# Microduino-Core.net
KiCad netlist of a schematic drawn in EAGLE
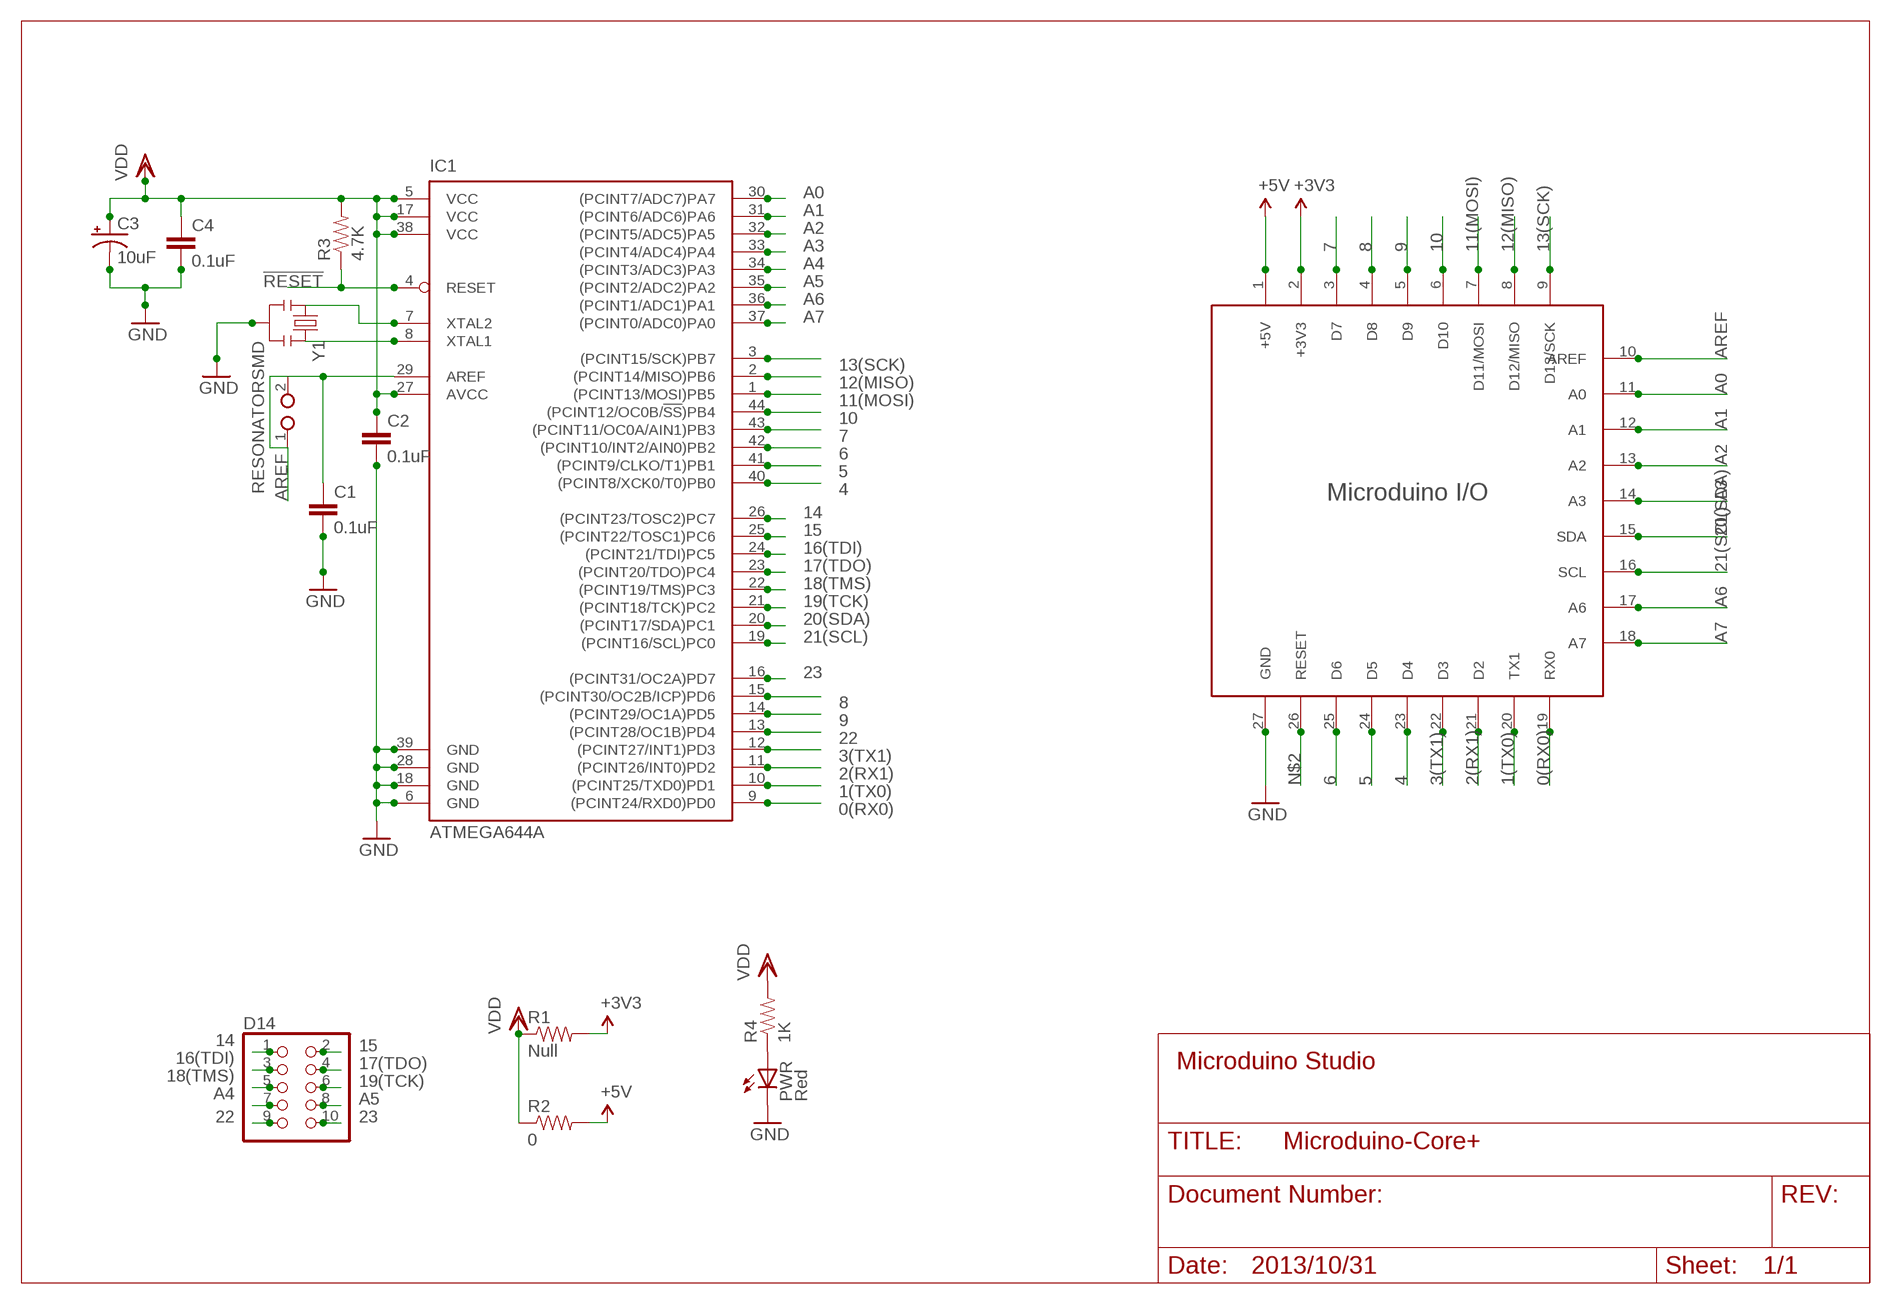
[diagram p0: schematic, sheet 1]

(export (version "E")
  (design (tool "Eeschema 10.0.6"))
  (components
    (comp (ref "C1")
      (value "0.1uF")
      (footprint "eagle-import:0603-CAP")
      (libsource (lib "eagle-import") (part "CAP0603-CAP"))
    )
    (comp (ref "C2")
      (value "0.1uF")
      (footprint "eagle-import:0603-CAP")
      (libsource (lib "eagle-import") (part "CAP0603-CAP"))
    )
    (comp (ref "C3")
      (value "10uF")
      (footprint "eagle-import:EIA3528")
      (libsource (lib "eagle-import") (part "CAP_POL3528"))
    )
    (comp (ref "C4")
      (value "0.1uF")
      (footprint "eagle-import:0603-CAP")
      (libsource (lib "eagle-import") (part "CAP0603-CAP"))
    )
    (comp (ref "D14")
      (value "PINHD-2X5")
      (footprint "eagle-import:2X05")
      (libsource (lib "eagle-import") (part "PINHD-2X5"))
    )
    (comp (ref "IC1")
      (value "ATMEGA644A")
      (footprint "eagle-import:TQFP44")
      (fields (field (name "MPN") "ATMEGA644PV-10AU"))
      (libsource (lib "eagle-import") (part "ATMEGA644A"))
    )
    (comp (ref "PWR")
      (value "Red")
      (footprint "eagle-import:0805-LED")
      (libsource (lib "eagle-import") (part "LED0805"))
    )
    (comp (ref "R1")
      (value "Null")
      (footprint "eagle-import:0603-RES")
      (libsource (lib "eagle-import") (part "RESISTOR0603-RES"))
    )
    (comp (ref "R2")
      (value "0")
      (footprint "eagle-import:0603-RES")
      (libsource (lib "eagle-import") (part "RESISTOR0603-RES"))
    )
    (comp (ref "R3")
      (value "4.7K")
      (footprint "eagle-import:0603-RES")
      (libsource (lib "eagle-import") (part "RESISTOR0603-RES"))
    )
    (comp (ref "R4")
      (value "1K")
      (footprint "eagle-import:0603-RES")
      (libsource (lib "eagle-import") (part "RESISTOR0603-RES"))
    )
    (comp (ref "U$1")
      (value "MICRDUINO-PIN/NORMAL+")
      (footprint "eagle-import:27UPIN-NORMAL+")
      (libsource (lib "eagle-import") (part "MICRDUINO-PIN/NORMAL+"))
    )
    (comp (ref "U$4")
      (value "JUMPER1-1")
      (footprint "eagle-import:JUMPER1-1")
      (libsource (lib "eagle-import") (part "JUMPER1-1"))
    )
    (comp (ref "Y1")
      (value "RESONATORSMD")
      (footprint "eagle-import:RESONATOR-SMD")
      (libsource (lib "eagle-import") (part "RESONATORSMD"))
    )
  )
  (nets
    (net (code "1") (name "+3V3") (class "Default")
      (node (ref "R1") (pin "2") (pinfunction "2_2") (pintype "passive"))
      (node (ref "U$1") (pin "2") (pinfunction "+3V3_2") (pintype "bidirectional"))
    )
    (net (code "2") (name "+5V") (class "Default")
      (node (ref "R2") (pin "2") (pinfunction "2_2") (pintype "passive"))
      (node (ref "U$1") (pin "1") (pinfunction "+5V_1") (pintype "bidirectional"))
    )
    (net (code "3") (name "/0(RX0)") (class "Default")
      (node (ref "IC1") (pin "9") (pinfunction "(PCINT24/RXD0)PD0_9") (pintype "bidirectional"))
      (node (ref "U$1") (pin "19") (pinfunction "RX0_19") (pintype "bidirectional"))
    )
    (net (code "4") (name "/1(TX0)") (class "Default")
      (node (ref "IC1") (pin "10") (pinfunction "(PCINT25/TXD0)PD1_10") (pintype "bidirectional"))
      (node (ref "U$1") (pin "20") (pinfunction "TX1_20") (pintype "bidirectional"))
    )
    (net (code "5") (name "/2(RX1)") (class "Default")
      (node (ref "IC1") (pin "11") (pinfunction "(PCINT26/INT0)PD2_11") (pintype "bidirectional"))
      (node (ref "U$1") (pin "21") (pinfunction "D2_21") (pintype "bidirectional"))
    )
    (net (code "6") (name "/3(TX1)") (class "Default")
      (node (ref "IC1") (pin "12") (pinfunction "(PCINT27/INT1)PD3_12") (pintype "bidirectional"))
      (node (ref "U$1") (pin "22") (pinfunction "D3_22") (pintype "bidirectional"))
    )
    (net (code "7") (name "/4") (class "Default")
      (node (ref "IC1") (pin "40") (pinfunction "(PCINT8/XCK0/T0)PB0_40") (pintype "bidirectional"))
      (node (ref "U$1") (pin "23") (pinfunction "D4_23") (pintype "bidirectional"))
    )
    (net (code "8") (name "/5") (class "Default")
      (node (ref "IC1") (pin "41") (pinfunction "(PCINT9/CLKO/T1)PB1_41") (pintype "bidirectional"))
      (node (ref "U$1") (pin "24") (pinfunction "D5_24") (pintype "bidirectional"))
    )
    (net (code "9") (name "/6") (class "Default")
      (node (ref "IC1") (pin "42") (pinfunction "(PCINT10/INT2/AIN0)PB2_42") (pintype "bidirectional"))
      (node (ref "U$1") (pin "25") (pinfunction "D6_25") (pintype "bidirectional"))
    )
    (net (code "10") (name "/7") (class "Default")
      (node (ref "IC1") (pin "43") (pinfunction "(PCINT11/OC0A/AIN1)PB3_43") (pintype "bidirectional"))
      (node (ref "U$1") (pin "3") (pinfunction "D7_3") (pintype "bidirectional"))
    )
    (net (code "11") (name "/8") (class "Default")
      (node (ref "IC1") (pin "15") (pinfunction "(PCINT30/OC2B/ICP)PD6_15") (pintype "bidirectional"))
      (node (ref "U$1") (pin "4") (pinfunction "D8_4") (pintype "bidirectional"))
    )
    (net (code "12") (name "/9") (class "Default")
      (node (ref "IC1") (pin "14") (pinfunction "(PCINT29/OC1A)PD5_14") (pintype "bidirectional"))
      (node (ref "U$1") (pin "5") (pinfunction "D9_5") (pintype "bidirectional"))
    )
    (net (code "13") (name "/10") (class "Default")
      (node (ref "IC1") (pin "44") (pinfunction "(PCINT12/OC0B/~{SS})PB4_44") (pintype "bidirectional"))
      (node (ref "U$1") (pin "6") (pinfunction "D10_6") (pintype "bidirectional"))
    )
    (net (code "14") (name "/11(MOSI)") (class "Default")
      (node (ref "IC1") (pin "1") (pinfunction "(PCINT13/MOSI)PB5_1") (pintype "bidirectional"))
      (node (ref "U$1") (pin "7") (pinfunction "D11/MOSI_7") (pintype "bidirectional"))
    )
    (net (code "15") (name "/12(MISO)") (class "Default")
      (node (ref "IC1") (pin "2") (pinfunction "(PCINT14/MISO)PB6_2") (pintype "bidirectional"))
      (node (ref "U$1") (pin "8") (pinfunction "D12/MISO_8") (pintype "bidirectional"))
    )
    (net (code "16") (name "/13(SCK)") (class "Default")
      (node (ref "IC1") (pin "3") (pinfunction "(PCINT15/SCK)PB7_3") (pintype "bidirectional"))
      (node (ref "U$1") (pin "9") (pinfunction "D13/SCK_9") (pintype "bidirectional"))
    )
    (net (code "17") (name "/14") (class "Default")
      (node (ref "D14") (pin "1") (pinfunction "1_1") (pintype "passive"))
      (node (ref "IC1") (pin "26") (pinfunction "(PCINT23/TOSC2)PC7_26") (pintype "output"))
    )
    (net (code "18") (name "/15") (class "Default")
      (node (ref "D14") (pin "2") (pinfunction "2_2") (pintype "passive"))
      (node (ref "IC1") (pin "25") (pinfunction "(PCINT22/TOSC1)PC6_25") (pintype "output"))
    )
    (net (code "19") (name "/16(TDI)") (class "Default")
      (node (ref "D14") (pin "3") (pinfunction "3_3") (pintype "passive"))
      (node (ref "IC1") (pin "24") (pinfunction "(PCINT21/TDI)PC5_24") (pintype "output"))
    )
    (net (code "20") (name "/17(TDO)") (class "Default")
      (node (ref "D14") (pin "4") (pinfunction "4_4") (pintype "passive"))
      (node (ref "IC1") (pin "23") (pinfunction "(PCINT20/TDO)PC4_23") (pintype "output"))
    )
    (net (code "21") (name "/18(TMS)") (class "Default")
      (node (ref "D14") (pin "5") (pinfunction "5_5") (pintype "passive"))
      (node (ref "IC1") (pin "22") (pinfunction "(PCINT19/TMS)PC3_22") (pintype "output"))
    )
    (net (code "22") (name "/19(TCK)") (class "Default")
      (node (ref "D14") (pin "6") (pinfunction "6_6") (pintype "passive"))
      (node (ref "IC1") (pin "21") (pinfunction "(PCINT18/TCK)PC2_21") (pintype "output"))
    )
    (net (code "23") (name "/20(SDA)") (class "Default")
      (node (ref "IC1") (pin "20") (pinfunction "(PCINT17/SDA)PC1_20") (pintype "output"))
      (node (ref "U$1") (pin "15") (pinfunction "SDA_15") (pintype "bidirectional"))
    )
    (net (code "24") (name "/21(SCL)") (class "Default")
      (node (ref "IC1") (pin "19") (pinfunction "(PCINT16/SCL)PC0_19") (pintype "output"))
      (node (ref "U$1") (pin "16") (pinfunction "SCL_16") (pintype "bidirectional"))
    )
    (net (code "25") (name "/22") (class "Default")
      (node (ref "D14") (pin "9") (pinfunction "9_9") (pintype "passive"))
      (node (ref "IC1") (pin "13") (pinfunction "(PCINT28/OC1B)PD4_13") (pintype "bidirectional"))
    )
    (net (code "26") (name "/23") (class "Default")
      (node (ref "D14") (pin "10") (pinfunction "10_10") (pintype "passive"))
      (node (ref "IC1") (pin "16") (pinfunction "(PCINT31/OC2A)PD7_16") (pintype "bidirectional"))
    )
    (net (code "27") (name "/A0") (class "Default")
      (node (ref "IC1") (pin "30") (pinfunction "(PCINT7/ADC7)PA7_30") (pintype "bidirectional"))
      (node (ref "U$1") (pin "11") (pinfunction "A0_11") (pintype "bidirectional"))
    )
    (net (code "28") (name "/A1") (class "Default")
      (node (ref "IC1") (pin "31") (pinfunction "(PCINT6/ADC6)PA6_31") (pintype "bidirectional"))
      (node (ref "U$1") (pin "12") (pinfunction "A1_12") (pintype "bidirectional"))
    )
    (net (code "29") (name "/A2") (class "Default")
      (node (ref "IC1") (pin "32") (pinfunction "(PCINT5/ADC5)PA5_32") (pintype "bidirectional"))
      (node (ref "U$1") (pin "13") (pinfunction "A2_13") (pintype "bidirectional"))
    )
    (net (code "30") (name "/A3") (class "Default")
      (node (ref "IC1") (pin "33") (pinfunction "(PCINT4/ADC4)PA4_33") (pintype "bidirectional"))
      (node (ref "U$1") (pin "14") (pinfunction "A3_14") (pintype "bidirectional"))
    )
    (net (code "31") (name "/A4") (class "Default")
      (node (ref "D14") (pin "7") (pinfunction "7_7") (pintype "passive"))
      (node (ref "IC1") (pin "34") (pinfunction "(PCINT3/ADC3)PA3_34") (pintype "bidirectional"))
    )
    (net (code "32") (name "/A5") (class "Default")
      (node (ref "D14") (pin "8") (pinfunction "8_8") (pintype "passive"))
      (node (ref "IC1") (pin "35") (pinfunction "(PCINT2/ADC2)PA2_35") (pintype "bidirectional"))
    )
    (net (code "33") (name "/A6") (class "Default")
      (node (ref "IC1") (pin "36") (pinfunction "(PCINT1/ADC1)PA1_36") (pintype "bidirectional"))
      (node (ref "U$1") (pin "17") (pinfunction "A6_17") (pintype "bidirectional"))
    )
    (net (code "34") (name "/A7") (class "Default")
      (node (ref "IC1") (pin "37") (pinfunction "(PCINT0/ADC0)PA0_37") (pintype "bidirectional"))
      (node (ref "U$1") (pin "18") (pinfunction "A7_18") (pintype "bidirectional"))
    )
    (net (code "35") (name "/AREF") (class "Default")
      (node (ref "C1") (pin "1") (pinfunction "1_1") (pintype "passive"))
      (node (ref "IC1") (pin "29") (pinfunction "AREF_29") (pintype "passive"))
      (node (ref "U$1") (pin "10") (pinfunction "AREF_10") (pintype "bidirectional"))
      (node (ref "U$4") (pin "1") (pinfunction "1_1") (pintype "bidirectional"))
      (node (ref "U$4") (pin "2") (pinfunction "2_2") (pintype "bidirectional"))
    )
    (net (code "36") (name "/N$2") (class "Default")
      (node (ref "U$1") (pin "26") (pinfunction "RESET_26") (pintype "bidirectional"))
    )
    (net (code "37") (name "/~{RESET}") (class "Default")
      (node (ref "IC1") (pin "4") (pinfunction "RESET_4") (pintype "input"))
      (node (ref "R3") (pin "1") (pinfunction "1_1") (pintype "passive"))
    )
    (net (code "38") (name "GND") (class "Default")
      (node (ref "C1") (pin "2") (pinfunction "2_2") (pintype "passive"))
      (node (ref "C2") (pin "2") (pinfunction "2_2") (pintype "passive"))
      (node (ref "C3") (pin "C") (pinfunction "-_C") (pintype "passive"))
      (node (ref "C4") (pin "2") (pinfunction "2_2") (pintype "passive"))
      (node (ref "IC1") (pin "18") (pinfunction "GND_18") (pintype "power_in"))
      (node (ref "IC1") (pin "28") (pinfunction "GND_28") (pintype "power_in"))
      (node (ref "IC1") (pin "39") (pinfunction "GND_39") (pintype "power_in"))
      (node (ref "IC1") (pin "6") (pinfunction "GND_6") (pintype "power_in"))
      (node (ref "PWR") (pin "C") (pinfunction "C_C") (pintype "passive"))
      (node (ref "U$1") (pin "27") (pinfunction "GND_27") (pintype "bidirectional"))
      (node (ref "Y1") (pin "2") (pinfunction "2_2") (pintype "passive"))
    )
    (net (code "39") (name "Net-(IC1-XTAL1)") (class "Default")
      (node (ref "IC1") (pin "8") (pinfunction "XTAL1_8") (pintype "bidirectional"))
      (node (ref "Y1") (pin "3") (pinfunction "3_3") (pintype "passive"))
    )
    (net (code "40") (name "Net-(IC1-XTAL2)") (class "Default")
      (node (ref "IC1") (pin "7") (pinfunction "XTAL2_7") (pintype "bidirectional"))
      (node (ref "Y1") (pin "1") (pinfunction "1_1") (pintype "passive"))
    )
    (net (code "41") (name "Net-(PWR-PadA)") (class "Default")
      (node (ref "PWR") (pin "A") (pinfunction "A_A") (pintype "passive"))
      (node (ref "R4") (pin "1") (pinfunction "1_1") (pintype "passive"))
    )
    (net (code "42") (name "VDD") (class "Default")
      (node (ref "C2") (pin "1") (pinfunction "1_1") (pintype "passive"))
      (node (ref "C3") (pin "A") (pinfunction "+_A") (pintype "passive"))
      (node (ref "C4") (pin "1") (pinfunction "1_1") (pintype "passive"))
      (node (ref "IC1") (pin "17") (pinfunction "VCC_17") (pintype "power_in"))
      (node (ref "IC1") (pin "27") (pinfunction "AVCC_27") (pintype "power_in"))
      (node (ref "IC1") (pin "38") (pinfunction "VCC_38") (pintype "power_in"))
      (node (ref "IC1") (pin "5") (pinfunction "VCC_5") (pintype "power_in"))
      (node (ref "R1") (pin "1") (pinfunction "1_1") (pintype "passive"))
      (node (ref "R2") (pin "1") (pinfunction "1_1") (pintype "passive"))
      (node (ref "R3") (pin "2") (pinfunction "2_2") (pintype "passive"))
      (node (ref "R4") (pin "2") (pinfunction "2_2") (pintype "passive"))
    )
  )
)
